# SwitchBoard_v3.net
KiCad netlist of a schematic drawn in Altium Designer
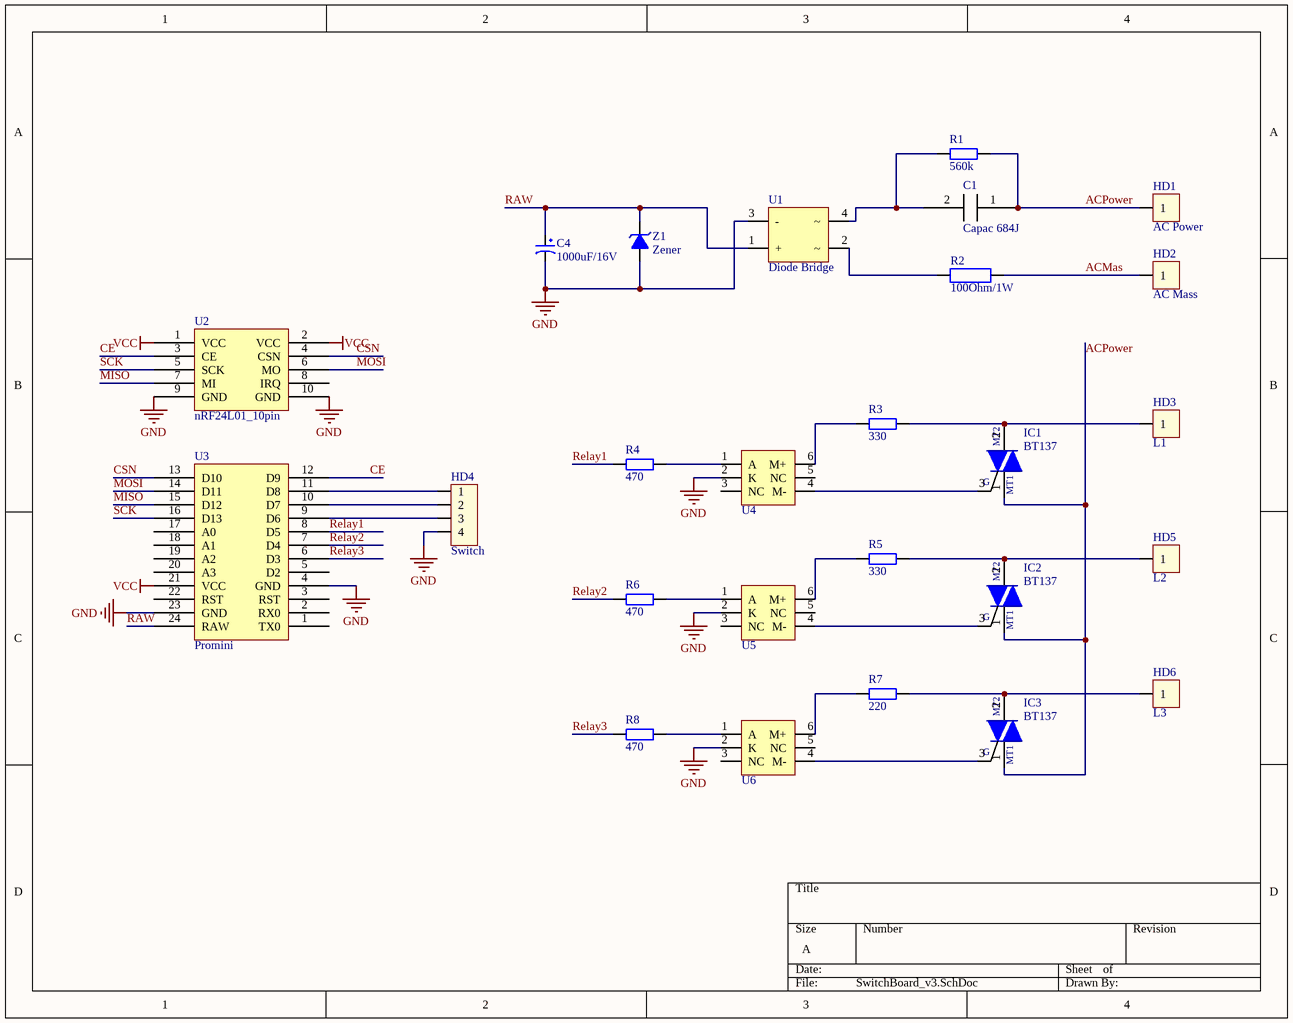
[diagram p0: SwitchBoard_v3.SchDoc]

(export (version "E")
  (design (tool "Eeschema 10.0.6"))
  (components
    (comp (ref "C1")
      (value "Capac 684J")
      (footprint "Tu keo 684J 400V")
      (libsource (lib "myLibs") (part "Tu keo 684J 400V"))
    )
    (comp (ref "C4")
      (value "1000uF/16V")
      (footprint "CP2/4")
      (description "Cap 2200uF/16V - 1000uF/50V")
      (libsource (lib "myLibs") (part "CP5"))
    )
    (comp (ref "HD1")
      (value "AC Power")
      (footprint "DOMINO1")
      (description "Header 2 (Green)")
      (libsource (lib "myLibs") (part "Domino1"))
    )
    (comp (ref "HD2")
      (value "AC Mass")
      (footprint "DOMINO1")
      (description "Header 2 (Green)")
      (libsource (lib "myLibs") (part "Domino1"))
    )
    (comp (ref "HD3")
      (value "L1")
      (footprint "DOMINO1")
      (description "Header 2 (Green)")
      (libsource (lib "myLibs") (part "Domino1"))
    )
    (comp (ref "HD4")
      (value "Switch")
      (footprint "DOMINO_MINI_4")
      (description "Header 2 (Green)")
      (libsource (lib "myLibs") (part "DominoMini4"))
    )
    (comp (ref "HD5")
      (value "L2")
      (footprint "DOMINO1")
      (description "Header 2 (Green)")
      (libsource (lib "myLibs") (part "Domino1"))
    )
    (comp (ref "HD6")
      (value "L3")
      (footprint "DOMINO1")
      (description "Header 2 (Green)")
      (libsource (lib "myLibs") (part "Domino1"))
    )
    (comp (ref "IC1")
      (value "BT137")
      (footprint "QTO-220")
      (description "Triacs - 8A")
      (libsource (lib "myLibs") (part "BT137"))
    )
    (comp (ref "IC2")
      (value "BT137")
      (footprint "QTO-220")
      (description "Triacs - 8A")
      (libsource (lib "myLibs") (part "BT137"))
    )
    (comp (ref "IC3")
      (value "BT137")
      (footprint "QTO-220")
      (description "Triacs - 8A")
      (libsource (lib "myLibs") (part "BT137"))
    )
    (comp (ref "R1")
      (value "560k")
      (footprint "R1/4W")
      (description "Resistor 1/4W")
      (libsource (lib "myLibs") (part "R1/4W"))
    )
    (comp (ref "R2")
      (value "100Ohm/1W")
      (footprint "RES1W")
      (description "1W Res Power")
      (fields (field (name "CREATOR") "Nguyen Ba Bien"))
      (libsource (lib "myLibs") (part "Res 1W"))
    )
    (comp (ref "R3")
      (value "330")
      (footprint "R1/4W")
      (description "Resistor 1/4W")
      (libsource (lib "myLibs") (part "R1/4W"))
    )
    (comp (ref "R4")
      (value "470")
      (footprint "R1/4W")
      (description "Resistor 1/4W")
      (libsource (lib "myLibs") (part "R1/4W"))
    )
    (comp (ref "R5")
      (value "330")
      (footprint "R1/4W")
      (description "Resistor 1/4W")
      (libsource (lib "myLibs") (part "R1/4W"))
    )
    (comp (ref "R6")
      (value "470")
      (footprint "R1/4W")
      (description "Resistor 1/4W")
      (libsource (lib "myLibs") (part "R1/4W"))
    )
    (comp (ref "R7")
      (value "220")
      (footprint "R1/4W")
      (description "Resistor 1/4W")
      (libsource (lib "myLibs") (part "R1/4W"))
    )
    (comp (ref "R8")
      (value "470")
      (footprint "R1/4W")
      (description "Resistor 1/4W")
      (libsource (lib "myLibs") (part "R1/4W"))
    )
    (comp (ref "U1")
      (value "Diode Bridge")
      (footprint "DIODE BRIDGE")
      (libsource (lib "myLibs") (part "Diode Bridge"))
    )
    (comp (ref "U2")
      (value "nRF24L01_10pin")
      (footprint "NRF24L01_10PIN")
      (libsource (lib "myLibs") (part "nRF24L01_10pin"))
    )
    (comp (ref "U3") (value "Promini") (footprint "Promini") (libsource (lib "myLibs") (part "Promini")))
    (comp (ref "U4") (value "MOC3021M") (footprint "MOC30XX") (libsource (lib "myLibs") (part "MOC3021M")))
    (comp (ref "U5") (value "MOC3021M") (footprint "MOC30XX") (libsource (lib "myLibs") (part "MOC3021M")))
    (comp (ref "U6") (value "MOC3021M") (footprint "MOC30XX") (libsource (lib "myLibs") (part "MOC3021M")))
    (comp (ref "Z1") (value "Zener") (footprint "D1A") (libsource (lib "myLibs") (part "Zener")))
  )
  (nets
    (net (code "1") (name "/ACMas") (class "Default")
      (node (ref "HD2") (pin "1") (pinfunction "1_1") (pintype "passive"))
      (node (ref "R2") (pin "2") (pinfunction "2_2") (pintype "passive"))
    )
    (net (code "2") (name "/ACPower") (class "Default")
      (node (ref "C1") (pin "1") (pinfunction "1_1") (pintype "passive"))
      (node (ref "HD1") (pin "1") (pinfunction "1_1") (pintype "passive"))
      (node (ref "IC1") (pin "1") (pinfunction "MT1_1") (pintype "passive"))
      (node (ref "IC2") (pin "1") (pinfunction "MT1_1") (pintype "passive"))
      (node (ref "IC3") (pin "1") (pinfunction "MT1_1") (pintype "passive"))
      (node (ref "R1") (pin "2") (pinfunction "2_2") (pintype "passive"))
    )
    (net (code "3") (name "/CE") (class "Default")
      (node (ref "U2") (pin "3") (pinfunction "CE_3") (pintype "passive"))
      (node (ref "U3") (pin "12") (pinfunction "D9_12") (pintype "passive"))
    )
    (net (code "4") (name "/CSN") (class "Default")
      (node (ref "U2") (pin "4") (pinfunction "CSN_4") (pintype "passive"))
      (node (ref "U3") (pin "13") (pinfunction "D10_13") (pintype "passive"))
    )
    (net (code "5") (name "/MISO") (class "Default")
      (node (ref "U2") (pin "7") (pinfunction "MI_7") (pintype "passive"))
      (node (ref "U3") (pin "15") (pinfunction "D12_15") (pintype "passive"))
    )
    (net (code "6") (name "/MOSI") (class "Default")
      (node (ref "U2") (pin "6") (pinfunction "MO_6") (pintype "passive"))
      (node (ref "U3") (pin "14") (pinfunction "D11_14") (pintype "passive"))
    )
    (net (code "7") (name "/RAW") (class "Default")
      (node (ref "C4") (pin "1") (pinfunction "1_1") (pintype "passive"))
      (node (ref "U1") (pin "1") (pinfunction "+_1") (pintype "passive"))
      (node (ref "U3") (pin "24") (pinfunction "RAW_24") (pintype "passive"))
      (node (ref "Z1") (pin "2") (pinfunction "K_2") (pintype "passive"))
    )
    (net (code "8") (name "/Relay1") (class "Default")
      (node (ref "R4") (pin "1") (pinfunction "1_1") (pintype "passive"))
      (node (ref "U3") (pin "8") (pinfunction "D5_8") (pintype "passive"))
    )
    (net (code "9") (name "/Relay2") (class "Default")
      (node (ref "R6") (pin "1") (pinfunction "1_1") (pintype "passive"))
      (node (ref "U3") (pin "7") (pinfunction "D4_7") (pintype "passive"))
    )
    (net (code "10") (name "/Relay3") (class "Default")
      (node (ref "R8") (pin "1") (pinfunction "1_1") (pintype "passive"))
      (node (ref "U3") (pin "6") (pinfunction "D3_6") (pintype "passive"))
    )
    (net (code "11") (name "/SCK") (class "Default")
      (node (ref "U2") (pin "5") (pinfunction "SCK_5") (pintype "passive"))
      (node (ref "U3") (pin "16") (pinfunction "D13_16") (pintype "passive"))
    )
    (net (code "12") (name "GND") (class "Default")
      (node (ref "C4") (pin "2") (pinfunction "2_2") (pintype "passive"))
      (node (ref "HD4") (pin "4") (pinfunction "4_4") (pintype "passive"))
      (node (ref "U1") (pin "3") (pinfunction "-_3") (pintype "passive"))
      (node (ref "U2") (pin "10") (pinfunction "GND_10") (pintype "passive"))
      (node (ref "U2") (pin "9") (pinfunction "GND_9") (pintype "passive"))
      (node (ref "U3") (pin "23") (pinfunction "GND_23") (pintype "passive"))
      (node (ref "U3") (pin "4") (pinfunction "GND_4") (pintype "passive"))
      (node (ref "U4") (pin "2") (pinfunction "K_2") (pintype "passive"))
      (node (ref "U5") (pin "2") (pinfunction "K_2") (pintype "passive"))
      (node (ref "U6") (pin "2") (pinfunction "K_2") (pintype "passive"))
      (node (ref "Z1") (pin "1") (pinfunction "A_1") (pintype "passive"))
    )
    (net (code "13") (name "Net-(C1-Pad2)") (class "Default")
      (node (ref "C1") (pin "2") (pinfunction "2_2") (pintype "passive"))
      (node (ref "R1") (pin "1") (pinfunction "1_1") (pintype "passive"))
      (node (ref "U1") (pin "4") (pinfunction "~_4") (pintype "passive"))
    )
    (net (code "14") (name "Net-(IC1-IN)") (class "Default")
      (node (ref "IC1") (pin "3") (pinfunction "IN_3") (pintype "passive"))
      (node (ref "U4") (pin "4") (pinfunction "M-_4") (pintype "passive"))
    )
    (net (code "15") (name "Net-(IC1-MT2)") (class "Default")
      (node (ref "HD3") (pin "1") (pinfunction "1_1") (pintype "passive"))
      (node (ref "IC1") (pin "2") (pinfunction "MT2_2") (pintype "passive"))
      (node (ref "R3") (pin "2") (pinfunction "2_2") (pintype "passive"))
    )
    (net (code "16") (name "Net-(IC2-IN)") (class "Default")
      (node (ref "IC2") (pin "3") (pinfunction "IN_3") (pintype "passive"))
      (node (ref "U5") (pin "4") (pinfunction "M-_4") (pintype "passive"))
    )
    (net (code "17") (name "Net-(IC2-MT2)") (class "Default")
      (node (ref "HD5") (pin "1") (pinfunction "1_1") (pintype "passive"))
      (node (ref "IC2") (pin "2") (pinfunction "MT2_2") (pintype "passive"))
      (node (ref "R5") (pin "2") (pinfunction "2_2") (pintype "passive"))
    )
    (net (code "18") (name "Net-(IC3-IN)") (class "Default")
      (node (ref "IC3") (pin "3") (pinfunction "IN_3") (pintype "passive"))
      (node (ref "U6") (pin "4") (pinfunction "M-_4") (pintype "passive"))
    )
    (net (code "19") (name "Net-(IC3-MT2)") (class "Default")
      (node (ref "HD6") (pin "1") (pinfunction "1_1") (pintype "passive"))
      (node (ref "IC3") (pin "2") (pinfunction "MT2_2") (pintype "passive"))
      (node (ref "R7") (pin "2") (pinfunction "2_2") (pintype "passive"))
    )
    (net (code "20") (name "Net-(R2-Pad1)") (class "Default")
      (node (ref "R2") (pin "1") (pinfunction "1_1") (pintype "passive"))
      (node (ref "U1") (pin "2") (pinfunction "~_2") (pintype "passive"))
    )
    (net (code "21") (name "Net-(U3-D6)") (class "Default")
      (node (ref "HD4") (pin "3") (pinfunction "3_3") (pintype "passive"))
      (node (ref "U3") (pin "9") (pinfunction "D6_9") (pintype "passive"))
    )
    (net (code "22") (name "Net-(U3-D7)") (class "Default")
      (node (ref "HD4") (pin "2") (pinfunction "2_2") (pintype "passive"))
      (node (ref "U3") (pin "10") (pinfunction "D7_10") (pintype "passive"))
    )
    (net (code "23") (name "Net-(U3-D8)") (class "Default")
      (node (ref "HD4") (pin "1") (pinfunction "1_1") (pintype "passive"))
      (node (ref "U3") (pin "11") (pinfunction "D8_11") (pintype "passive"))
    )
    (net (code "24") (name "Net-(U4-A)") (class "Default")
      (node (ref "R4") (pin "2") (pinfunction "2_2") (pintype "passive"))
      (node (ref "U4") (pin "1") (pinfunction "A_1") (pintype "passive"))
    )
    (net (code "25") (name "Net-(U4-M+)") (class "Default")
      (node (ref "R3") (pin "1") (pinfunction "1_1") (pintype "passive"))
      (node (ref "U4") (pin "6") (pinfunction "M+_6") (pintype "passive"))
    )
    (net (code "26") (name "Net-(U5-A)") (class "Default")
      (node (ref "R6") (pin "2") (pinfunction "2_2") (pintype "passive"))
      (node (ref "U5") (pin "1") (pinfunction "A_1") (pintype "passive"))
    )
    (net (code "27") (name "Net-(U5-M+)") (class "Default")
      (node (ref "R5") (pin "1") (pinfunction "1_1") (pintype "passive"))
      (node (ref "U5") (pin "6") (pinfunction "M+_6") (pintype "passive"))
    )
    (net (code "28") (name "Net-(U6-A)") (class "Default")
      (node (ref "R8") (pin "2") (pinfunction "2_2") (pintype "passive"))
      (node (ref "U6") (pin "1") (pinfunction "A_1") (pintype "passive"))
    )
    (net (code "29") (name "Net-(U6-M+)") (class "Default")
      (node (ref "R7") (pin "1") (pinfunction "1_1") (pintype "passive"))
      (node (ref "U6") (pin "6") (pinfunction "M+_6") (pintype "passive"))
    )
    (net (code "30") (name "VCC") (class "Default")
      (node (ref "U2") (pin "1") (pinfunction "VCC_1") (pintype "passive"))
      (node (ref "U2") (pin "2") (pinfunction "VCC_2") (pintype "passive"))
      (node (ref "U3") (pin "21") (pinfunction "VCC_21") (pintype "passive"))
    )
    (net (code "31") (name "unconnected-(U2-IRQ-Pad8)") (class "Default")
      (node (ref "U2") (pin "8") (pinfunction "IRQ_8") (pintype "passive"))
    )
    (net (code "32") (name "unconnected-(U3-A0-Pad17)") (class "Default")
      (node (ref "U3") (pin "17") (pinfunction "A0_17") (pintype "passive"))
    )
    (net (code "33") (name "unconnected-(U3-A1-Pad18)") (class "Default")
      (node (ref "U3") (pin "18") (pinfunction "A1_18") (pintype "passive"))
    )
    (net (code "34") (name "unconnected-(U3-A2-Pad19)") (class "Default")
      (node (ref "U3") (pin "19") (pinfunction "A2_19") (pintype "passive"))
    )
    (net (code "35") (name "unconnected-(U3-A3-Pad20)") (class "Default")
      (node (ref "U3") (pin "20") (pinfunction "A3_20") (pintype "passive"))
    )
    (net (code "36") (name "unconnected-(U3-D2-Pad5)") (class "Default")
      (node (ref "U3") (pin "5") (pinfunction "D2_5") (pintype "passive"))
    )
    (net (code "37") (name "unconnected-(U3-RST-Pad3)") (class "Default")
      (node (ref "U3") (pin "3") (pinfunction "RST_3") (pintype "passive"))
    )
    (net (code "38") (name "unconnected-(U3-RST-Pad22)") (class "Default")
      (node (ref "U3") (pin "22") (pinfunction "RST_22") (pintype "passive"))
    )
    (net (code "39") (name "unconnected-(U3-RX0-Pad2)") (class "Default")
      (node (ref "U3") (pin "2") (pinfunction "RX0_2") (pintype "passive"))
    )
    (net (code "40") (name "unconnected-(U3-TX0-Pad1)") (class "Default")
      (node (ref "U3") (pin "1") (pinfunction "TX0_1") (pintype "passive"))
    )
    (net (code "41") (name "unconnected-(U4-NC-Pad3)") (class "Default")
      (node (ref "U4") (pin "3") (pinfunction "NC_3") (pintype "passive"))
    )
    (net (code "42") (name "unconnected-(U4-NC-Pad5)") (class "Default")
      (node (ref "U4") (pin "5") (pinfunction "NC_5") (pintype "passive"))
    )
    (net (code "43") (name "unconnected-(U5-NC-Pad3)") (class "Default")
      (node (ref "U5") (pin "3") (pinfunction "NC_3") (pintype "passive"))
    )
    (net (code "44") (name "unconnected-(U5-NC-Pad5)") (class "Default")
      (node (ref "U5") (pin "5") (pinfunction "NC_5") (pintype "passive"))
    )
    (net (code "45") (name "unconnected-(U6-NC-Pad3)") (class "Default")
      (node (ref "U6") (pin "3") (pinfunction "NC_3") (pintype "passive"))
    )
    (net (code "46") (name "unconnected-(U6-NC-Pad5)") (class "Default")
      (node (ref "U6") (pin "5") (pinfunction "NC_5") (pintype "passive"))
    )
  )
)
